# 03_-_Power.net
KiCad netlist of a schematic drawn in Altium Designer
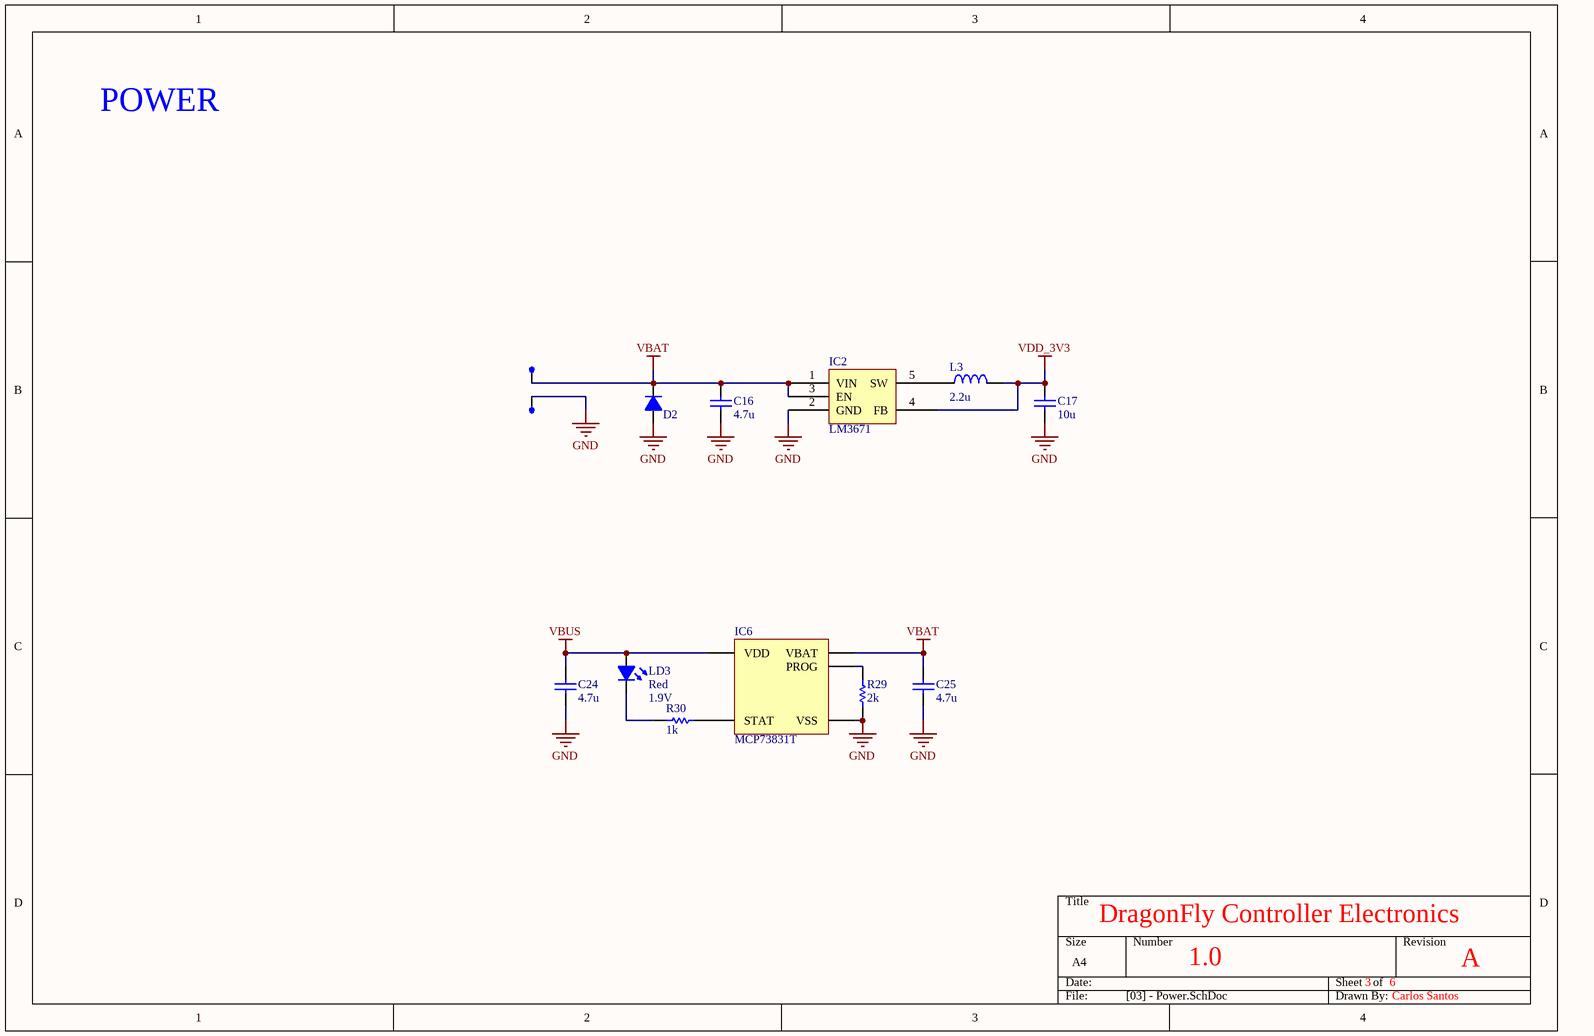
[diagram p0: [03] - Power.SchDoc]

(export (version "E")
  (design (tool "Eeschema 10.0.6"))
  (components
    (comp (ref "C16")
      (value "4.7u")
      (footprint "0603 - Capacitor")
      (fields (field (name "Comment") "Capacitor"))
      (libsource (lib "Mine") (part "Capacitor"))
    )
    (comp (ref "C17")
      (value "10u")
      (footprint "0603 - Capacitor")
      (fields (field (name "Comment") "Capacitor"))
      (libsource (lib "Mine") (part "Capacitor"))
    )
    (comp (ref "C24")
      (value "4.7u")
      (footprint "0402 - Capacitor")
      (fields (field (name "Comment") "Capacitor"))
      (libsource (lib "Mine") (part "Capacitor"))
    )
    (comp (ref "C25")
      (value "4.7u")
      (footprint "0402 - Capacitor")
      (fields (field (name "Comment") "Capacitor"))
      (libsource (lib "Mine") (part "Capacitor"))
    )
    (comp (ref "D2") (value "Diode") (footprint "SOD 923") (libsource (lib "Mine") (part "Diode")))
    (comp (ref "IC2")
      (value "LM3671")
      (footprint "SOT 23 - 5")
      (fields (field (name "DIGIKEY PART #") "LM3671MF-3.3/NOPBCT-ND"))
      (libsource (lib "Mine") (part "LM3671"))
    )
    (comp (ref "IC6")
      (value "MCP73831T")
      (footprint "QFN50P300X200X100_HS-9N")
      (description "MCP73831T-2ACI/OTCT-ND")
      (fields (field (name "DIGIKEY PART #") "MCP73831T-2ACI/MCCT-ND"))
      (libsource (lib "Mine") (part "Lipo Charger"))
    )
    (comp (ref "L3")
      (value "2.2u")
      (footprint "MDMK2020")
      (fields (field (name "Comment") "Inductor"))
      (libsource (lib "Mine") (part "Inductor"))
    )
    (comp (ref "LD3")
      (value "Led")
      (footprint "0603 - led")
      (fields (field (name "COLOR") "Red") (field (name "VF") "1.9V"))
      (libsource (lib "Mine") (part "Led"))
    )
    (comp (ref "R29")
      (value "2k")
      (footprint "0402 - Resistor")
      (fields (field (name "Comment") "Resistor"))
      (libsource (lib "Mine") (part "Resistor"))
    )
    (comp (ref "R30")
      (value "1k")
      (footprint "0402 - Resistor")
      (fields (field (name "Comment") "Resistor"))
      (libsource (lib "Mine") (part "Resistor"))
    )
    (comp (ref "SP3")
      (value "Signal Point")
      (footprint "Signal_point_1mm")
      (libsource (lib "Mine") (part "Signal Point"))
    )
    (comp (ref "SP4")
      (value "Signal Point")
      (footprint "Signal_point_1mm")
      (libsource (lib "Mine") (part "Signal Point"))
    )
  )
  (nets
    (net (code "1") (name "GND") (class "Default")
      (node (ref "C16") (pin "1") (pinfunction "1_1") (pintype "passive"))
      (node (ref "C17") (pin "1") (pinfunction "1_1") (pintype "passive"))
      (node (ref "C24") (pin "1") (pinfunction "1_1") (pintype "passive"))
      (node (ref "C25") (pin "1") (pinfunction "1_1") (pintype "passive"))
      (node (ref "D2") (pin "1") (pinfunction "A_1") (pintype "passive"))
      (node (ref "IC2") (pin "2") (pinfunction "GND_2") (pintype "passive"))
      (node (ref "IC6") (pin "2") (pinfunction "VSS_2") (pintype "passive"))
      (node (ref "R29") (pin "1") (pinfunction "1_1") (pintype "passive"))
      (node (ref "SP4") (pin "0") (pinfunction "VIN_0") (pintype "passive"))
    )
    (net (code "2") (name "Net-(IC2-SW)") (class "Default")
      (node (ref "IC2") (pin "5") (pinfunction "SW_5") (pintype "passive"))
      (node (ref "L3") (pin "1") (pinfunction "1_1") (pintype "passive"))
    )
    (net (code "3") (name "Net-(IC6-PROG)") (class "Default")
      (node (ref "IC6") (pin "5") (pinfunction "PROG_5") (pintype "passive"))
      (node (ref "R29") (pin "2") (pinfunction "2_2") (pintype "passive"))
    )
    (net (code "4") (name "Net-(IC6-STAT)") (class "Default")
      (node (ref "IC6") (pin "1") (pinfunction "STAT_1") (pintype "passive"))
      (node (ref "R30") (pin "1") (pinfunction "1_1") (pintype "passive"))
    )
    (net (code "5") (name "Net-(LD3-K)") (class "Default")
      (node (ref "LD3") (pin "2") (pinfunction "K_2") (pintype "passive"))
      (node (ref "R30") (pin "2") (pinfunction "2_2") (pintype "passive"))
    )
    (net (code "6") (name "VBAT") (class "Default")
      (node (ref "C16") (pin "2") (pinfunction "2_2") (pintype "passive"))
      (node (ref "C25") (pin "2") (pinfunction "2_2") (pintype "passive"))
      (node (ref "D2") (pin "2") (pinfunction "K_2") (pintype "passive"))
      (node (ref "IC2") (pin "1") (pinfunction "VIN_1") (pintype "passive"))
      (node (ref "IC2") (pin "3") (pinfunction "EN_3") (pintype "passive"))
      (node (ref "IC6") (pin "3") (pinfunction "VBAT_3") (pintype "passive"))
      (node (ref "SP3") (pin "0") (pinfunction "VIN_0") (pintype "passive"))
    )
    (net (code "7") (name "VBUS") (class "Default")
      (node (ref "C24") (pin "2") (pinfunction "2_2") (pintype "passive"))
      (node (ref "IC6") (pin "4") (pinfunction "VDD_4") (pintype "passive"))
      (node (ref "LD3") (pin "1") (pinfunction "A_1") (pintype "passive"))
    )
    (net (code "8") (name "VDD_3V3") (class "Default")
      (node (ref "C17") (pin "2") (pinfunction "2_2") (pintype "passive"))
      (node (ref "IC2") (pin "4") (pinfunction "FB_4") (pintype "passive"))
      (node (ref "L3") (pin "2") (pinfunction "2_2") (pintype "passive"))
    )
  )
)
